# driver.net
KiCad netlist of a schematic drawn in EAGLE
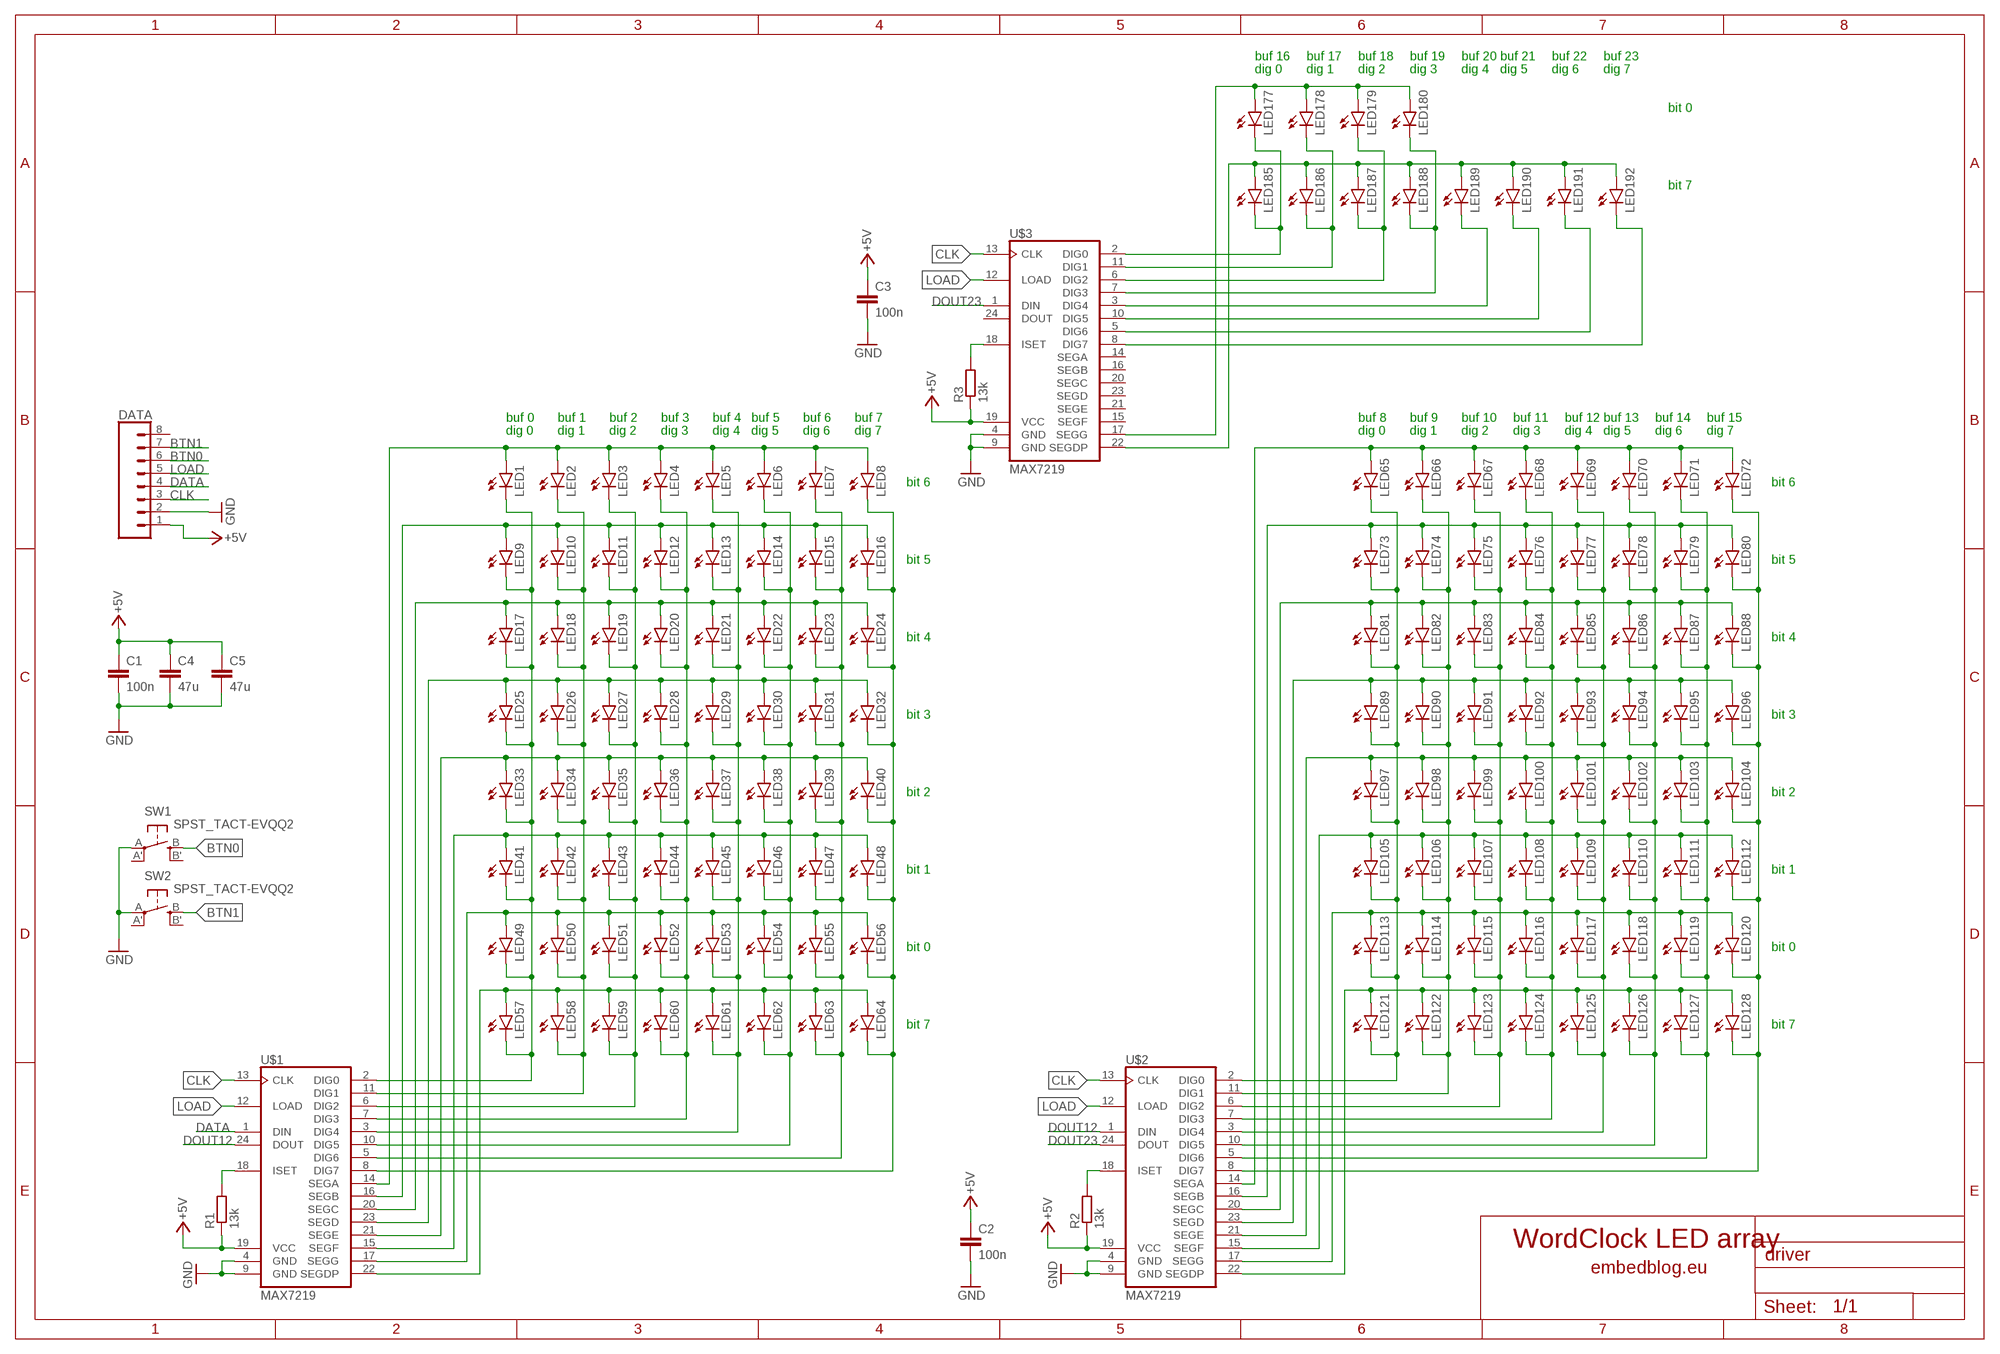
[diagram p0: schematic, sheet 1]

(export (version "E")
  (design (tool "Eeschema 10.0.6"))
  (components
    (comp (ref "C1")
      (value "100n")
      (footprint "eagle-import:C1206")
      (libsource (lib "eagle-import") (part "C-EUC1206"))
    )
    (comp (ref "C2")
      (value "100n")
      (footprint "eagle-import:C1206")
      (libsource (lib "eagle-import") (part "C-EUC1206"))
    )
    (comp (ref "C3")
      (value "100n")
      (footprint "eagle-import:C1206")
      (libsource (lib "eagle-import") (part "C-EUC1206"))
    )
    (comp (ref "C4")
      (value "47u")
      (footprint "eagle-import:C1206")
      (libsource (lib "eagle-import") (part "C-EUC1206"))
    )
    (comp (ref "C5")
      (value "47u")
      (footprint "eagle-import:C1206")
      (libsource (lib "eagle-import") (part "C-EUC1206"))
    )
    (comp (ref "DATA")
      (value "CONN_08\"")
      (footprint "eagle-import:1X08")
      (libsource (lib "eagle-import") (part "CONN_08{dblquote}"))
    )
    (comp (ref "LED1")
      (value "LEDCHIPLED_1206")
      (footprint "eagle-import:CHIPLED_1206")
      (libsource (lib "eagle-import") (part "LEDCHIPLED_1206"))
    )
    (comp (ref "LED2")
      (value "LEDCHIPLED_1206")
      (footprint "eagle-import:CHIPLED_1206")
      (libsource (lib "eagle-import") (part "LEDCHIPLED_1206"))
    )
    (comp (ref "LED3")
      (value "LEDCHIPLED_1206")
      (footprint "eagle-import:CHIPLED_1206")
      (libsource (lib "eagle-import") (part "LEDCHIPLED_1206"))
    )
    (comp (ref "LED4")
      (value "LEDCHIPLED_1206")
      (footprint "eagle-import:CHIPLED_1206")
      (libsource (lib "eagle-import") (part "LEDCHIPLED_1206"))
    )
    (comp (ref "LED5")
      (value "LEDCHIPLED_1206")
      (footprint "eagle-import:CHIPLED_1206")
      (libsource (lib "eagle-import") (part "LEDCHIPLED_1206"))
    )
    (comp (ref "LED6")
      (value "LEDCHIPLED_1206")
      (footprint "eagle-import:CHIPLED_1206")
      (libsource (lib "eagle-import") (part "LEDCHIPLED_1206"))
    )
    (comp (ref "LED7")
      (value "LEDCHIPLED_1206")
      (footprint "eagle-import:CHIPLED_1206")
      (libsource (lib "eagle-import") (part "LEDCHIPLED_1206"))
    )
    (comp (ref "LED8")
      (value "LEDCHIPLED_1206")
      (footprint "eagle-import:CHIPLED_1206")
      (libsource (lib "eagle-import") (part "LEDCHIPLED_1206"))
    )
    (comp (ref "LED9")
      (value "LEDCHIPLED_1206")
      (footprint "eagle-import:CHIPLED_1206")
      (libsource (lib "eagle-import") (part "LEDCHIPLED_1206"))
    )
    (comp (ref "LED10")
      (value "LEDCHIPLED_1206")
      (footprint "eagle-import:CHIPLED_1206")
      (libsource (lib "eagle-import") (part "LEDCHIPLED_1206"))
    )
    (comp (ref "LED11")
      (value "LEDCHIPLED_1206")
      (footprint "eagle-import:CHIPLED_1206")
      (libsource (lib "eagle-import") (part "LEDCHIPLED_1206"))
    )
    (comp (ref "LED12")
      (value "LEDCHIPLED_1206")
      (footprint "eagle-import:CHIPLED_1206")
      (libsource (lib "eagle-import") (part "LEDCHIPLED_1206"))
    )
    (comp (ref "LED13")
      (value "LEDCHIPLED_1206")
      (footprint "eagle-import:CHIPLED_1206")
      (libsource (lib "eagle-import") (part "LEDCHIPLED_1206"))
    )
    (comp (ref "LED14")
      (value "LEDCHIPLED_1206")
      (footprint "eagle-import:CHIPLED_1206")
      (libsource (lib "eagle-import") (part "LEDCHIPLED_1206"))
    )
    (comp (ref "LED15")
      (value "LEDCHIPLED_1206")
      (footprint "eagle-import:CHIPLED_1206")
      (libsource (lib "eagle-import") (part "LEDCHIPLED_1206"))
    )
    (comp (ref "LED16")
      (value "LEDCHIPLED_1206")
      (footprint "eagle-import:CHIPLED_1206")
      (libsource (lib "eagle-import") (part "LEDCHIPLED_1206"))
    )
    (comp (ref "LED17")
      (value "LEDCHIPLED_1206")
      (footprint "eagle-import:CHIPLED_1206")
      (libsource (lib "eagle-import") (part "LEDCHIPLED_1206"))
    )
    (comp (ref "LED18")
      (value "LEDCHIPLED_1206")
      (footprint "eagle-import:CHIPLED_1206")
      (libsource (lib "eagle-import") (part "LEDCHIPLED_1206"))
    )
    (comp (ref "LED19")
      (value "LEDCHIPLED_1206")
      (footprint "eagle-import:CHIPLED_1206")
      (libsource (lib "eagle-import") (part "LEDCHIPLED_1206"))
    )
    (comp (ref "LED20")
      (value "LEDCHIPLED_1206")
      (footprint "eagle-import:CHIPLED_1206")
      (libsource (lib "eagle-import") (part "LEDCHIPLED_1206"))
    )
    (comp (ref "LED21")
      (value "LEDCHIPLED_1206")
      (footprint "eagle-import:CHIPLED_1206")
      (libsource (lib "eagle-import") (part "LEDCHIPLED_1206"))
    )
    (comp (ref "LED22")
      (value "LEDCHIPLED_1206")
      (footprint "eagle-import:CHIPLED_1206")
      (libsource (lib "eagle-import") (part "LEDCHIPLED_1206"))
    )
    (comp (ref "LED23")
      (value "LEDCHIPLED_1206")
      (footprint "eagle-import:CHIPLED_1206")
      (libsource (lib "eagle-import") (part "LEDCHIPLED_1206"))
    )
    (comp (ref "LED24")
      (value "LEDCHIPLED_1206")
      (footprint "eagle-import:CHIPLED_1206")
      (libsource (lib "eagle-import") (part "LEDCHIPLED_1206"))
    )
    (comp (ref "LED25")
      (value "LEDCHIPLED_1206")
      (footprint "eagle-import:CHIPLED_1206")
      (libsource (lib "eagle-import") (part "LEDCHIPLED_1206"))
    )
    (comp (ref "LED26")
      (value "LEDCHIPLED_1206")
      (footprint "eagle-import:CHIPLED_1206")
      (libsource (lib "eagle-import") (part "LEDCHIPLED_1206"))
    )
    (comp (ref "LED27")
      (value "LEDCHIPLED_1206")
      (footprint "eagle-import:CHIPLED_1206")
      (libsource (lib "eagle-import") (part "LEDCHIPLED_1206"))
    )
    (comp (ref "LED28")
      (value "LEDCHIPLED_1206")
      (footprint "eagle-import:CHIPLED_1206")
      (libsource (lib "eagle-import") (part "LEDCHIPLED_1206"))
    )
    (comp (ref "LED29")
      (value "LEDCHIPLED_1206")
      (footprint "eagle-import:CHIPLED_1206")
      (libsource (lib "eagle-import") (part "LEDCHIPLED_1206"))
    )
    (comp (ref "LED30")
      (value "LEDCHIPLED_1206")
      (footprint "eagle-import:CHIPLED_1206")
      (libsource (lib "eagle-import") (part "LEDCHIPLED_1206"))
    )
    (comp (ref "LED31")
      (value "LEDCHIPLED_1206")
      (footprint "eagle-import:CHIPLED_1206")
      (libsource (lib "eagle-import") (part "LEDCHIPLED_1206"))
    )
    (comp (ref "LED32")
      (value "LEDCHIPLED_1206")
      (footprint "eagle-import:CHIPLED_1206")
      (libsource (lib "eagle-import") (part "LEDCHIPLED_1206"))
    )
    (comp (ref "LED33")
      (value "LEDCHIPLED_1206")
      (footprint "eagle-import:CHIPLED_1206")
      (libsource (lib "eagle-import") (part "LEDCHIPLED_1206"))
    )
    (comp (ref "LED34")
      (value "LEDCHIPLED_1206")
      (footprint "eagle-import:CHIPLED_1206")
      (libsource (lib "eagle-import") (part "LEDCHIPLED_1206"))
    )
    (comp (ref "LED35")
      (value "LEDCHIPLED_1206")
      (footprint "eagle-import:CHIPLED_1206")
      (libsource (lib "eagle-import") (part "LEDCHIPLED_1206"))
    )
    (comp (ref "LED36")
      (value "LEDCHIPLED_1206")
      (footprint "eagle-import:CHIPLED_1206")
      (libsource (lib "eagle-import") (part "LEDCHIPLED_1206"))
    )
    (comp (ref "LED37")
      (value "LEDCHIPLED_1206")
      (footprint "eagle-import:CHIPLED_1206")
      (libsource (lib "eagle-import") (part "LEDCHIPLED_1206"))
    )
    (comp (ref "LED38")
      (value "LEDCHIPLED_1206")
      (footprint "eagle-import:CHIPLED_1206")
      (libsource (lib "eagle-import") (part "LEDCHIPLED_1206"))
    )
    (comp (ref "LED39")
      (value "LEDCHIPLED_1206")
      (footprint "eagle-import:CHIPLED_1206")
      (libsource (lib "eagle-import") (part "LEDCHIPLED_1206"))
    )
    (comp (ref "LED40")
      (value "LEDCHIPLED_1206")
      (footprint "eagle-import:CHIPLED_1206")
      (libsource (lib "eagle-import") (part "LEDCHIPLED_1206"))
    )
    (comp (ref "LED41")
      (value "LEDCHIPLED_1206")
      (footprint "eagle-import:CHIPLED_1206")
      (libsource (lib "eagle-import") (part "LEDCHIPLED_1206"))
    )
    (comp (ref "LED42")
      (value "LEDCHIPLED_1206")
      (footprint "eagle-import:CHIPLED_1206")
      (libsource (lib "eagle-import") (part "LEDCHIPLED_1206"))
    )
    (comp (ref "LED43")
      (value "LEDCHIPLED_1206")
      (footprint "eagle-import:CHIPLED_1206")
      (libsource (lib "eagle-import") (part "LEDCHIPLED_1206"))
    )
    (comp (ref "LED44")
      (value "LEDCHIPLED_1206")
      (footprint "eagle-import:CHIPLED_1206")
      (libsource (lib "eagle-import") (part "LEDCHIPLED_1206"))
    )
    (comp (ref "LED45")
      (value "LEDCHIPLED_1206")
      (footprint "eagle-import:CHIPLED_1206")
      (libsource (lib "eagle-import") (part "LEDCHIPLED_1206"))
    )
    (comp (ref "LED46")
      (value "LEDCHIPLED_1206")
      (footprint "eagle-import:CHIPLED_1206")
      (libsource (lib "eagle-import") (part "LEDCHIPLED_1206"))
    )
    (comp (ref "LED47")
      (value "LEDCHIPLED_1206")
      (footprint "eagle-import:CHIPLED_1206")
      (libsource (lib "eagle-import") (part "LEDCHIPLED_1206"))
    )
    (comp (ref "LED48")
      (value "LEDCHIPLED_1206")
      (footprint "eagle-import:CHIPLED_1206")
      (libsource (lib "eagle-import") (part "LEDCHIPLED_1206"))
    )
    (comp (ref "LED49")
      (value "LEDCHIPLED_1206")
      (footprint "eagle-import:CHIPLED_1206")
      (libsource (lib "eagle-import") (part "LEDCHIPLED_1206"))
    )
    (comp (ref "LED50")
      (value "LEDCHIPLED_1206")
      (footprint "eagle-import:CHIPLED_1206")
      (libsource (lib "eagle-import") (part "LEDCHIPLED_1206"))
    )
    (comp (ref "LED51")
      (value "LEDCHIPLED_1206")
      (footprint "eagle-import:CHIPLED_1206")
      (libsource (lib "eagle-import") (part "LEDCHIPLED_1206"))
    )
    (comp (ref "LED52")
      (value "LEDCHIPLED_1206")
      (footprint "eagle-import:CHIPLED_1206")
      (libsource (lib "eagle-import") (part "LEDCHIPLED_1206"))
    )
    (comp (ref "LED53")
      (value "LEDCHIPLED_1206")
      (footprint "eagle-import:CHIPLED_1206")
      (libsource (lib "eagle-import") (part "LEDCHIPLED_1206"))
    )
    (comp (ref "LED54")
      (value "LEDCHIPLED_1206")
      (footprint "eagle-import:CHIPLED_1206")
      (libsource (lib "eagle-import") (part "LEDCHIPLED_1206"))
    )
    (comp (ref "LED55")
      (value "LEDCHIPLED_1206")
      (footprint "eagle-import:CHIPLED_1206")
      (libsource (lib "eagle-import") (part "LEDCHIPLED_1206"))
    )
    (comp (ref "LED56")
      (value "LEDCHIPLED_1206")
      (footprint "eagle-import:CHIPLED_1206")
      (libsource (lib "eagle-import") (part "LEDCHIPLED_1206"))
    )
    (comp (ref "LED57")
      (value "LEDCHIPLED_1206")
      (footprint "eagle-import:CHIPLED_1206")
      (libsource (lib "eagle-import") (part "LEDCHIPLED_1206"))
    )
    (comp (ref "LED58")
      (value "LEDCHIPLED_1206")
      (footprint "eagle-import:CHIPLED_1206")
      (libsource (lib "eagle-import") (part "LEDCHIPLED_1206"))
    )
    (comp (ref "LED59")
      (value "LEDCHIPLED_1206")
      (footprint "eagle-import:CHIPLED_1206")
      (libsource (lib "eagle-import") (part "LEDCHIPLED_1206"))
    )
    (comp (ref "LED60")
      (value "LEDCHIPLED_1206")
      (footprint "eagle-import:CHIPLED_1206")
      (libsource (lib "eagle-import") (part "LEDCHIPLED_1206"))
    )
    (comp (ref "LED61")
      (value "LEDCHIPLED_1206")
      (footprint "eagle-import:CHIPLED_1206")
      (libsource (lib "eagle-import") (part "LEDCHIPLED_1206"))
    )
    (comp (ref "LED62")
      (value "LEDCHIPLED_1206")
      (footprint "eagle-import:CHIPLED_1206")
      (libsource (lib "eagle-import") (part "LEDCHIPLED_1206"))
    )
    (comp (ref "LED63")
      (value "LEDCHIPLED_1206")
      (footprint "eagle-import:CHIPLED_1206")
      (libsource (lib "eagle-import") (part "LEDCHIPLED_1206"))
    )
    (comp (ref "LED64")
      (value "LEDCHIPLED_1206")
      (footprint "eagle-import:CHIPLED_1206")
      (libsource (lib "eagle-import") (part "LEDCHIPLED_1206"))
    )
    (comp (ref "LED65")
      (value "LEDCHIPLED_1206")
      (footprint "eagle-import:CHIPLED_1206")
      (libsource (lib "eagle-import") (part "LEDCHIPLED_1206"))
    )
    (comp (ref "LED66")
      (value "LEDCHIPLED_1206")
      (footprint "eagle-import:CHIPLED_1206")
      (libsource (lib "eagle-import") (part "LEDCHIPLED_1206"))
    )
    (comp (ref "LED67")
      (value "LEDCHIPLED_1206")
      (footprint "eagle-import:CHIPLED_1206")
      (libsource (lib "eagle-import") (part "LEDCHIPLED_1206"))
    )
    (comp (ref "LED68")
      (value "LEDCHIPLED_1206")
      (footprint "eagle-import:CHIPLED_1206")
      (libsource (lib "eagle-import") (part "LEDCHIPLED_1206"))
    )
    (comp (ref "LED69")
      (value "LEDCHIPLED_1206")
      (footprint "eagle-import:CHIPLED_1206")
      (libsource (lib "eagle-import") (part "LEDCHIPLED_1206"))
    )
    (comp (ref "LED70")
      (value "LEDCHIPLED_1206")
      (footprint "eagle-import:CHIPLED_1206")
      (libsource (lib "eagle-import") (part "LEDCHIPLED_1206"))
    )
    (comp (ref "LED71")
      (value "LEDCHIPLED_1206")
      (footprint "eagle-import:CHIPLED_1206")
      (libsource (lib "eagle-import") (part "LEDCHIPLED_1206"))
    )
    (comp (ref "LED72")
      (value "LEDCHIPLED_1206")
      (footprint "eagle-import:CHIPLED_1206")
      (libsource (lib "eagle-import") (part "LEDCHIPLED_1206"))
    )
    (comp (ref "LED73")
      (value "LEDCHIPLED_1206")
      (footprint "eagle-import:CHIPLED_1206")
      (libsource (lib "eagle-import") (part "LEDCHIPLED_1206"))
    )
    (comp (ref "LED74")
      (value "LEDCHIPLED_1206")
      (footprint "eagle-import:CHIPLED_1206")
      (libsource (lib "eagle-import") (part "LEDCHIPLED_1206"))
    )
    (comp (ref "LED75")
      (value "LEDCHIPLED_1206")
      (footprint "eagle-import:CHIPLED_1206")
      (libsource (lib "eagle-import") (part "LEDCHIPLED_1206"))
    )
    (comp (ref "LED76")
      (value "LEDCHIPLED_1206")
      (footprint "eagle-import:CHIPLED_1206")
      (libsource (lib "eagle-import") (part "LEDCHIPLED_1206"))
    )
    (comp (ref "LED77")
      (value "LEDCHIPLED_1206")
      (footprint "eagle-import:CHIPLED_1206")
      (libsource (lib "eagle-import") (part "LEDCHIPLED_1206"))
    )
    (comp (ref "LED78")
      (value "LEDCHIPLED_1206")
      (footprint "eagle-import:CHIPLED_1206")
      (libsource (lib "eagle-import") (part "LEDCHIPLED_1206"))
    )
    (comp (ref "LED79")
      (value "LEDCHIPLED_1206")
      (footprint "eagle-import:CHIPLED_1206")
      (libsource (lib "eagle-import") (part "LEDCHIPLED_1206"))
    )
    (comp (ref "LED80")
      (value "LEDCHIPLED_1206")
      (footprint "eagle-import:CHIPLED_1206")
      (libsource (lib "eagle-import") (part "LEDCHIPLED_1206"))
    )
    (comp (ref "LED81")
      (value "LEDCHIPLED_1206")
      (footprint "eagle-import:CHIPLED_1206")
      (libsource (lib "eagle-import") (part "LEDCHIPLED_1206"))
    )
    (comp (ref "LED82")
      (value "LEDCHIPLED_1206")
      (footprint "eagle-import:CHIPLED_1206")
      (libsource (lib "eagle-import") (part "LEDCHIPLED_1206"))
    )
    (comp (ref "LED83")
      (value "LEDCHIPLED_1206")
      (footprint "eagle-import:CHIPLED_1206")
      (libsource (lib "eagle-import") (part "LEDCHIPLED_1206"))
    )
    (comp (ref "LED84")
      (value "LEDCHIPLED_1206")
      (footprint "eagle-import:CHIPLED_1206")
      (libsource (lib "eagle-import") (part "LEDCHIPLED_1206"))
    )
    (comp (ref "LED85")
      (value "LEDCHIPLED_1206")
      (footprint "eagle-import:CHIPLED_1206")
      (libsource (lib "eagle-import") (part "LEDCHIPLED_1206"))
    )
    (comp (ref "LED86")
      (value "LEDCHIPLED_1206")
      (footprint "eagle-import:CHIPLED_1206")
      (libsource (lib "eagle-import") (part "LEDCHIPLED_1206"))
    )
    (comp (ref "LED87")
      (value "LEDCHIPLED_1206")
      (footprint "eagle-import:CHIPLED_1206")
      (libsource (lib "eagle-import") (part "LEDCHIPLED_1206"))
    )
    (comp (ref "LED88")
      (value "LEDCHIPLED_1206")
      (footprint "eagle-import:CHIPLED_1206")
      (libsource (lib "eagle-import") (part "LEDCHIPLED_1206"))
    )
    (comp (ref "LED89")
      (value "LEDCHIPLED_1206")
      (footprint "eagle-import:CHIPLED_1206")
      (libsource (lib "eagle-import") (part "LEDCHIPLED_1206"))
    )
    (comp (ref "LED90")
      (value "LEDCHIPLED_1206")
      (footprint "eagle-import:CHIPLED_1206")
      (libsource (lib "eagle-import") (part "LEDCHIPLED_1206"))
    )
    (comp (ref "LED91")
      (value "LEDCHIPLED_1206")
      (footprint "eagle-import:CHIPLED_1206")
      (libsource (lib "eagle-import") (part "LEDCHIPLED_1206"))
    )
    (comp (ref "LED92")
      (value "LEDCHIPLED_1206")
      (footprint "eagle-import:CHIPLED_1206")
      (libsource (lib "eagle-import") (part "LEDCHIPLED_1206"))
    )
    (comp (ref "LED93")
      (value "LEDCHIPLED_1206")
      (footprint "eagle-import:CHIPLED_1206")
      (libsource (lib "eagle-import") (part "LEDCHIPLED_1206"))
    )
    (comp (ref "LED94")
      (value "LEDCHIPLED_1206")
      (footprint "eagle-import:CHIPLED_1206")
      (libsource (lib "eagle-import") (part "LEDCHIPLED_1206"))
    )
    (comp (ref "LED95")
      (value "LEDCHIPLED_1206")
      (footprint "eagle-import:CHIPLED_1206")
      (libsource (lib "eagle-import") (part "LEDCHIPLED_1206"))
    )
    (comp (ref "LED96")
      (value "LEDCHIPLED_1206")
      (footprint "eagle-import:CHIPLED_1206")
      (libsource (lib "eagle-import") (part "LEDCHIPLED_1206"))
    )
    (comp (ref "LED97")
      (value "LEDCHIPLED_1206")
      (footprint "eagle-import:CHIPLED_1206")
      (libsource (lib "eagle-import") (part "LEDCHIPLED_1206"))
    )
    (comp (ref "LED98")
      (value "LEDCHIPLED_1206")
      (footprint "eagle-import:CHIPLED_1206")
      (libsource (lib "eagle-import") (part "LEDCHIPLED_1206"))
    )
    (comp (ref "LED99")
      (value "LEDCHIPLED_1206")
      (footprint "eagle-import:CHIPLED_1206")
      (libsource (lib "eagle-import") (part "LEDCHIPLED_1206"))
    )
    (comp (ref "LED100")
      (value "LEDCHIPLED_1206")
      (footprint "eagle-import:CHIPLED_1206")
      (libsource (lib "eagle-import") (part "LEDCHIPLED_1206"))
    )
    (comp (ref "LED101")
      (value "LEDCHIPLED_1206")
      (footprint "eagle-import:CHIPLED_1206")
      (libsource (lib "eagle-import") (part "LEDCHIPLED_1206"))
    )
    (comp (ref "LED102")
      (value "LEDCHIPLED_1206")
      (footprint "eagle-import:CHIPLED_1206")
      (libsource (lib "eagle-import") (part "LEDCHIPLED_1206"))
    )
    (comp (ref "LED103")
      (value "LEDCHIPLED_1206")
      (footprint "eagle-import:CHIPLED_1206")
      (libsource (lib "eagle-import") (part "LEDCHIPLED_1206"))
    )
    (comp (ref "LED104")
      (value "LEDCHIPLED_1206")
      (footprint "eagle-import:CHIPLED_1206")
      (libsource (lib "eagle-import") (part "LEDCHIPLED_1206"))
    )
    (comp (ref "LED105")
      (value "LEDCHIPLED_1206")
      (footprint "eagle-import:CHIPLED_1206")
      (libsource (lib "eagle-import") (part "LEDCHIPLED_1206"))
    )
    (comp (ref "LED106")
      (value "LEDCHIPLED_1206")
      (footprint "eagle-import:CHIPLED_1206")
      (libsource (lib "eagle-import") (part "LEDCHIPLED_1206"))
    )
    (comp (ref "LED107")
      (value "LEDCHIPLED_1206")
      (footprint "eagle-import:CHIPLED_1206")
      (libsource (lib "eagle-import") (part "LEDCHIPLED_1206"))
    )
    (comp (ref "LED108")
      (value "LEDCHIPLED_1206")
      (footprint "eagle-import:CHIPLED_1206")
      (libsource (lib "eagle-import") (part "LEDCHIPLED_1206"))
    )
    (comp (ref "LED109")
      (value "LEDCHIPLED_1206")
      (footprint "eagle-import:CHIPLED_1206")
      (libsource (lib "eagle-import") (part "LEDCHIPLED_1206"))
    )
    (comp (ref "LED110")
      (value "LEDCHIPLED_1206")
      (footprint "eagle-import:CHIPLED_1206")
      (libsource (lib "eagle-import") (part "LEDCHIPLED_1206"))
    )
    (comp (ref "LED111")
      (value "LEDCHIPLED_1206")
      (footprint "eagle-import:CHIPLED_1206")
      (libsource (lib "eagle-import") (part "LEDCHIPLED_1206"))
    )
    (comp (ref "LED112")
      (value "LEDCHIPLED_1206")
      (footprint "eagle-import:CHIPLED_1206")
      (libsource (lib "eagle-import") (part "LEDCHIPLED_1206"))
    )
    (comp (ref "LED113")
      (value "LEDCHIPLED_1206")
      (footprint "eagle-import:CHIPLED_1206")
      (libsource (lib "eagle-import") (part "LEDCHIPLED_1206"))
    )
    (comp (ref "LED114")
      (value "LEDCHIPLED_1206")
      (footprint "eagle-import:CHIPLED_1206")
      (libsource (lib "eagle-import") (part "LEDCHIPLED_1206"))
    )
    (comp (ref "LED115")
      (value "LEDCHIPLED_1206")
      (footprint "eagle-import:CHIPLED_1206")
      (libsource (lib "eagle-import") (part "LEDCHIPLED_1206"))
    )
    (comp (ref "LED116")
      (value "LEDCHIPLED_1206")
      (footprint "eagle-import:CHIPLED_1206")
      (libsource (lib "eagle-import") (part "LEDCHIPLED_1206"))
    )
    (comp (ref "LED117")
      (value "LEDCHIPLED_1206")
      (footprint "eagle-import:CHIPLED_1206")
      (libsource (lib "eagle-import") (part "LEDCHIPLED_1206"))
    )
    (comp (ref "LED118")
      (value "LEDCHIPLED_1206")
      (footprint "eagle-import:CHIPLED_1206")
      (libsource (lib "eagle-import") (part "LEDCHIPLED_1206"))
    )
    (comp (ref "LED119")
      (value "LEDCHIPLED_1206")
      (footprint "eagle-import:CHIPLED_1206")
      (libsource (lib "eagle-import") (part "LEDCHIPLED_1206"))
    )
    (comp (ref "LED120")
      (value "LEDCHIPLED_1206")
      (footprint "eagle-import:CHIPLED_1206")
      (libsource (lib "eagle-import") (part "LEDCHIPLED_1206"))
    )
    (comp (ref "LED121")
      (value "LEDCHIPLED_1206")
      (footprint "eagle-import:CHIPLED_1206")
      (libsource (lib "eagle-import") (part "LEDCHIPLED_1206"))
    )
    (comp (ref "LED122")
      (value "LEDCHIPLED_1206")
      (footprint "eagle-import:CHIPLED_1206")
      (libsource (lib "eagle-import") (part "LEDCHIPLED_1206"))
    )
    (comp (ref "LED123")
      (value "LEDCHIPLED_1206")
      (footprint "eagle-import:CHIPLED_1206")
      (libsource (lib "eagle-import") (part "LEDCHIPLED_1206"))
    )
    (comp (ref "LED124")
      (value "LEDCHIPLED_1206")
      (footprint "eagle-import:CHIPLED_1206")
      (libsource (lib "eagle-import") (part "LEDCHIPLED_1206"))
    )
    (comp (ref "LED125")
      (value "LEDCHIPLED_1206")
      (footprint "eagle-import:CHIPLED_1206")
      (libsource (lib "eagle-import") (part "LEDCHIPLED_1206"))
    )
    (comp (ref "LED126")
      (value "LEDCHIPLED_1206")
      (footprint "eagle-import:CHIPLED_1206")
      (libsource (lib "eagle-import") (part "LEDCHIPLED_1206"))
    )
    (comp (ref "LED127")
      (value "LEDCHIPLED_1206")
      (footprint "eagle-import:CHIPLED_1206")
      (libsource (lib "eagle-import") (part "LEDCHIPLED_1206"))
    )
    (comp (ref "LED128")
      (value "LEDCHIPLED_1206")
      (footprint "eagle-import:CHIPLED_1206")
      (libsource (lib "eagle-import") (part "LEDCHIPLED_1206"))
    )
    (comp (ref "LED177")
      (value "LEDCHIPLED_1206")
      (footprint "eagle-import:CHIPLED_1206")
      (libsource (lib "eagle-import") (part "LEDCHIPLED_1206"))
    )
    (comp (ref "LED178")
      (value "LEDCHIPLED_1206")
      (footprint "eagle-import:CHIPLED_1206")
      (libsource (lib "eagle-import") (part "LEDCHIPLED_1206"))
    )
    (comp (ref "LED179")
      (value "LEDCHIPLED_1206")
      (footprint "eagle-import:CHIPLED_1206")
      (libsource (lib "eagle-import") (part "LEDCHIPLED_1206"))
    )
    (comp (ref "LED180")
      (value "LEDCHIPLED_1206")
      (footprint "eagle-import:CHIPLED_1206")
      (libsource (lib "eagle-import") (part "LEDCHIPLED_1206"))
    )
    (comp (ref "LED185")
      (value "LEDCHIPLED_1206")
      (footprint "eagle-import:CHIPLED_1206")
      (libsource (lib "eagle-import") (part "LEDCHIPLED_1206"))
    )
    (comp (ref "LED186")
      (value "LEDCHIPLED_1206")
      (footprint "eagle-import:CHIPLED_1206")
      (libsource (lib "eagle-import") (part "LEDCHIPLED_1206"))
    )
    (comp (ref "LED187")
      (value "LEDCHIPLED_1206")
      (footprint "eagle-import:CHIPLED_1206")
      (libsource (lib "eagle-import") (part "LEDCHIPLED_1206"))
    )
    (comp (ref "LED188")
      (value "LEDCHIPLED_1206")
      (footprint "eagle-import:CHIPLED_1206")
      (libsource (lib "eagle-import") (part "LEDCHIPLED_1206"))
    )
    (comp (ref "LED189")
      (value "LEDCHIPLED_1206")
      (footprint "eagle-import:CHIPLED_1206")
      (libsource (lib "eagle-import") (part "LEDCHIPLED_1206"))
    )
    (comp (ref "LED190")
      (value "LEDCHIPLED_1206")
      (footprint "eagle-import:CHIPLED_1206")
      (libsource (lib "eagle-import") (part "LEDCHIPLED_1206"))
    )
    (comp (ref "LED191")
      (value "LEDCHIPLED_1206")
      (footprint "eagle-import:CHIPLED_1206")
      (libsource (lib "eagle-import") (part "LEDCHIPLED_1206"))
    )
    (comp (ref "LED192")
      (value "LEDCHIPLED_1206")
      (footprint "eagle-import:CHIPLED_1206")
      (libsource (lib "eagle-import") (part "LEDCHIPLED_1206"))
    )
    (comp (ref "R1")
      (value "13k")
      (footprint "eagle-import:R1206")
      (libsource (lib "eagle-import") (part "R-EU_R1206"))
    )
    (comp (ref "R2")
      (value "13k")
      (footprint "eagle-import:R1206")
      (libsource (lib "eagle-import") (part "R-EU_R1206"))
    )
    (comp (ref "R3")
      (value "13k")
      (footprint "eagle-import:R1206")
      (libsource (lib "eagle-import") (part "R-EU_R1206"))
    )
    (comp (ref "SW1")
      (value "SPST_TACT-EVQQ2")
      (footprint "eagle-import:EVQ-Q2")
      (libsource (lib "eagle-import") (part "SPST_TACT-EVQQ2"))
    )
    (comp (ref "SW2")
      (value "SPST_TACT-EVQQ2")
      (footprint "eagle-import:EVQ-Q2")
      (libsource (lib "eagle-import") (part "SPST_TACT-EVQQ2"))
    )
    (comp (ref "U$1")
      (value "MAX7219")
      (footprint "eagle-import:SO24W")
      (libsource (lib "eagle-import") (part "MAX7219"))
    )
    (comp (ref "U$2")
      (value "MAX7219")
      (footprint "eagle-import:SO24W")
      (libsource (lib "eagle-import") (part "MAX7219"))
    )
    (comp (ref "U$3")
      (value "MAX7219")
      (footprint "eagle-import:SO24W")
      (libsource (lib "eagle-import") (part "MAX7219"))
    )
  )
  (nets
    (net (code "1") (name "+5V") (class "Default")
      (node (ref "C1") (pin "1") (pinfunction "1_1") (pintype "passive"))
      (node (ref "C2") (pin "1") (pinfunction "1_1") (pintype "passive"))
      (node (ref "C3") (pin "1") (pinfunction "1_1") (pintype "passive"))
      (node (ref "C4") (pin "1") (pinfunction "1_1") (pintype "passive"))
      (node (ref "C5") (pin "1") (pinfunction "1_1") (pintype "passive"))
      (node (ref "DATA") (pin "1") (pinfunction "1_1") (pintype "passive"))
      (node (ref "R1") (pin "1") (pinfunction "1_1") (pintype "passive"))
      (node (ref "R2") (pin "1") (pinfunction "1_1") (pintype "passive"))
      (node (ref "R3") (pin "1") (pinfunction "1_1") (pintype "passive"))
      (node (ref "U$1") (pin "19") (pinfunction "VCC_19") (pintype "power_in"))
      (node (ref "U$2") (pin "19") (pinfunction "VCC_19") (pintype "power_in"))
      (node (ref "U$3") (pin "19") (pinfunction "VCC_19") (pintype "power_in"))
    )
    (net (code "2") (name "/DATA") (class "Default")
      (node (ref "DATA") (pin "4") (pinfunction "4_4") (pintype "passive"))
      (node (ref "U$1") (pin "1") (pinfunction "DIN_1") (pintype "input"))
    )
    (net (code "3") (name "/DOUT12") (class "Default")
      (node (ref "U$1") (pin "24") (pinfunction "DOUT_24") (pintype "output"))
      (node (ref "U$2") (pin "1") (pinfunction "DIN_1") (pintype "input"))
    )
    (net (code "4") (name "/DOUT23") (class "Default")
      (node (ref "U$2") (pin "24") (pinfunction "DOUT_24") (pintype "output"))
      (node (ref "U$3") (pin "1") (pinfunction "DIN_1") (pintype "input"))
    )
    (net (code "5") (name "BTN0") (class "Default")
      (node (ref "DATA") (pin "6") (pinfunction "6_6") (pintype "passive"))
      (node (ref "SW1") (pin "B") (pinfunction "S_B") (pintype "passive"))
    )
    (net (code "6") (name "BTN1") (class "Default")
      (node (ref "DATA") (pin "7") (pinfunction "7_7") (pintype "passive"))
      (node (ref "SW2") (pin "B") (pinfunction "S_B") (pintype "passive"))
    )
    (net (code "7") (name "CLK") (class "Default")
      (node (ref "DATA") (pin "3") (pinfunction "3_3") (pintype "passive"))
      (node (ref "U$1") (pin "13") (pinfunction "CLK_13") (pintype "input"))
      (node (ref "U$2") (pin "13") (pinfunction "CLK_13") (pintype "input"))
      (node (ref "U$3") (pin "13") (pinfunction "CLK_13") (pintype "input"))
    )
    (net (code "8") (name "GND") (class "Default")
      (node (ref "C1") (pin "2") (pinfunction "2_2") (pintype "passive"))
      (node (ref "C2") (pin "2") (pinfunction "2_2") (pintype "passive"))
      (node (ref "C3") (pin "2") (pinfunction "2_2") (pintype "passive"))
      (node (ref "C4") (pin "2") (pinfunction "2_2") (pintype "passive"))
      (node (ref "C5") (pin "2") (pinfunction "2_2") (pintype "passive"))
      (node (ref "DATA") (pin "2") (pinfunction "2_2") (pintype "passive"))
      (node (ref "SW1") (pin "A") (pinfunction "P_A") (pintype "passive"))
      (node (ref "SW2") (pin "A") (pinfunction "P_A") (pintype "passive"))
      (node (ref "U$1") (pin "4") (pinfunction "GND_4") (pintype "power_in"))
      (node (ref "U$1") (pin "9") (pinfunction "GND_9") (pintype "power_in"))
      (node (ref "U$2") (pin "4") (pinfunction "GND_4") (pintype "power_in"))
      (node (ref "U$2") (pin "9") (pinfunction "GND_9") (pintype "power_in"))
      (node (ref "U$3") (pin "4") (pinfunction "GND_4") (pintype "power_in"))
      (node (ref "U$3") (pin "9") (pinfunction "GND_9") (pintype "power_in"))
    )
    (net (code "9") (name "LOAD") (class "Default")
      (node (ref "DATA") (pin "5") (pinfunction "5_5") (pintype "passive"))
      (node (ref "U$1") (pin "12") (pinfunction "LOAD_12") (pintype "input"))
      (node (ref "U$2") (pin "12") (pinfunction "LOAD_12") (pintype "input"))
      (node (ref "U$3") (pin "12") (pinfunction "LOAD_12") (pintype "input"))
    )
    (net (code "10") (name "Net-(U$1-DIG0)") (class "Default")
      (node (ref "LED1") (pin "C") (pinfunction "C_C") (pintype "passive"))
      (node (ref "LED17") (pin "C") (pinfunction "C_C") (pintype "passive"))
      (node (ref "LED25") (pin "C") (pinfunction "C_C") (pintype "passive"))
      (node (ref "LED33") (pin "C") (pinfunction "C_C") (pintype "passive"))
      (node (ref "LED41") (pin "C") (pinfunction "C_C") (pintype "passive"))
      (node (ref "LED49") (pin "C") (pinfunction "C_C") (pintype "passive"))
      (node (ref "LED57") (pin "C") (pinfunction "C_C") (pintype "passive"))
      (node (ref "LED9") (pin "C") (pinfunction "C_C") (pintype "passive"))
      (node (ref "U$1") (pin "2") (pinfunction "DIG0_2") (pintype "output"))
    )
    (net (code "11") (name "Net-(U$1-DIG1)") (class "Default")
      (node (ref "LED10") (pin "C") (pinfunction "C_C") (pintype "passive"))
      (node (ref "LED18") (pin "C") (pinfunction "C_C") (pintype "passive"))
      (node (ref "LED2") (pin "C") (pinfunction "C_C") (pintype "passive"))
      (node (ref "LED26") (pin "C") (pinfunction "C_C") (pintype "passive"))
      (node (ref "LED34") (pin "C") (pinfunction "C_C") (pintype "passive"))
      (node (ref "LED42") (pin "C") (pinfunction "C_C") (pintype "passive"))
      (node (ref "LED50") (pin "C") (pinfunction "C_C") (pintype "passive"))
      (node (ref "LED58") (pin "C") (pinfunction "C_C") (pintype "passive"))
      (node (ref "U$1") (pin "11") (pinfunction "DIG1_11") (pintype "output"))
    )
    (net (code "12") (name "Net-(U$1-DIG2)") (class "Default")
      (node (ref "LED11") (pin "C") (pinfunction "C_C") (pintype "passive"))
      (node (ref "LED19") (pin "C") (pinfunction "C_C") (pintype "passive"))
      (node (ref "LED27") (pin "C") (pinfunction "C_C") (pintype "passive"))
      (node (ref "LED3") (pin "C") (pinfunction "C_C") (pintype "passive"))
      (node (ref "LED35") (pin "C") (pinfunction "C_C") (pintype "passive"))
      (node (ref "LED43") (pin "C") (pinfunction "C_C") (pintype "passive"))
      (node (ref "LED51") (pin "C") (pinfunction "C_C") (pintype "passive"))
      (node (ref "LED59") (pin "C") (pinfunction "C_C") (pintype "passive"))
      (node (ref "U$1") (pin "6") (pinfunction "DIG2_6") (pintype "output"))
    )
    (net (code "13") (name "Net-(U$1-DIG3)") (class "Default")
      (node (ref "LED12") (pin "C") (pinfunction "C_C") (pintype "passive"))
      (node (ref "LED20") (pin "C") (pinfunction "C_C") (pintype "passive"))
      (node (ref "LED28") (pin "C") (pinfunction "C_C") (pintype "passive"))
      (node (ref "LED36") (pin "C") (pinfunction "C_C") (pintype "passive"))
      (node (ref "LED4") (pin "C") (pinfunction "C_C") (pintype "passive"))
      (node (ref "LED44") (pin "C") (pinfunction "C_C") (pintype "passive"))
      (node (ref "LED52") (pin "C") (pinfunction "C_C") (pintype "passive"))
      (node (ref "LED60") (pin "C") (pinfunction "C_C") (pintype "passive"))
      (node (ref "U$1") (pin "7") (pinfunction "DIG3_7") (pintype "output"))
    )
    (net (code "14") (name "Net-(U$1-DIG4)") (class "Default")
      (node (ref "LED13") (pin "C") (pinfunction "C_C") (pintype "passive"))
      (node (ref "LED21") (pin "C") (pinfunction "C_C") (pintype "passive"))
      (node (ref "LED29") (pin "C") (pinfunction "C_C") (pintype "passive"))
      (node (ref "LED37") (pin "C") (pinfunction "C_C") (pintype "passive"))
      (node (ref "LED45") (pin "C") (pinfunction "C_C") (pintype "passive"))
      (node (ref "LED5") (pin "C") (pinfunction "C_C") (pintype "passive"))
      (node (ref "LED53") (pin "C") (pinfunction "C_C") (pintype "passive"))
      (node (ref "LED61") (pin "C") (pinfunction "C_C") (pintype "passive"))
      (node (ref "U$1") (pin "3") (pinfunction "DIG4_3") (pintype "output"))
    )
    (net (code "15") (name "Net-(U$1-DIG5)") (class "Default")
      (node (ref "LED14") (pin "C") (pinfunction "C_C") (pintype "passive"))
      (node (ref "LED22") (pin "C") (pinfunction "C_C") (pintype "passive"))
      (node (ref "LED30") (pin "C") (pinfunction "C_C") (pintype "passive"))
      (node (ref "LED38") (pin "C") (pinfunction "C_C") (pintype "passive"))
      (node (ref "LED46") (pin "C") (pinfunction "C_C") (pintype "passive"))
      (node (ref "LED54") (pin "C") (pinfunction "C_C") (pintype "passive"))
      (node (ref "LED6") (pin "C") (pinfunction "C_C") (pintype "passive"))
      (node (ref "LED62") (pin "C") (pinfunction "C_C") (pintype "passive"))
      (node (ref "U$1") (pin "10") (pinfunction "DIG5_10") (pintype "output"))
    )
    (net (code "16") (name "Net-(U$1-DIG6)") (class "Default")
      (node (ref "LED15") (pin "C") (pinfunction "C_C") (pintype "passive"))
      (node (ref "LED23") (pin "C") (pinfunction "C_C") (pintype "passive"))
      (node (ref "LED31") (pin "C") (pinfunction "C_C") (pintype "passive"))
      (node (ref "LED39") (pin "C") (pinfunction "C_C") (pintype "passive"))
      (node (ref "LED47") (pin "C") (pinfunction "C_C") (pintype "passive"))
      (node (ref "LED55") (pin "C") (pinfunction "C_C") (pintype "passive"))
      (node (ref "LED63") (pin "C") (pinfunction "C_C") (pintype "passive"))
      (node (ref "LED7") (pin "C") (pinfunction "C_C") (pintype "passive"))
      (node (ref "U$1") (pin "5") (pinfunction "DIG6_5") (pintype "output"))
    )
    (net (code "17") (name "Net-(U$1-DIG7)") (class "Default")
      (node (ref "LED16") (pin "C") (pinfunction "C_C") (pintype "passive"))
      (node (ref "LED24") (pin "C") (pinfunction "C_C") (pintype "passive"))
      (node (ref "LED32") (pin "C") (pinfunction "C_C") (pintype "passive"))
      (node (ref "LED40") (pin "C") (pinfunction "C_C") (pintype "passive"))
      (node (ref "LED48") (pin "C") (pinfunction "C_C") (pintype "passive"))
      (node (ref "LED56") (pin "C") (pinfunction "C_C") (pintype "passive"))
      (node (ref "LED64") (pin "C") (pinfunction "C_C") (pintype "passive"))
      (node (ref "LED8") (pin "C") (pinfunction "C_C") (pintype "passive"))
      (node (ref "U$1") (pin "8") (pinfunction "DIG7_8") (pintype "output"))
    )
    (net (code "18") (name "Net-(U$1-ISET)") (class "Default")
      (node (ref "R1") (pin "2") (pinfunction "2_2") (pintype "passive"))
      (node (ref "U$1") (pin "18") (pinfunction "ISET_18") (pintype "input"))
    )
    (net (code "19") (name "Net-(U$1-SEGA)") (class "Default")
      (node (ref "LED1") (pin "A") (pinfunction "A_A") (pintype "passive"))
      (node (ref "LED2") (pin "A") (pinfunction "A_A") (pintype "passive"))
      (node (ref "LED3") (pin "A") (pinfunction "A_A") (pintype "passive"))
      (node (ref "LED4") (pin "A") (pinfunction "A_A") (pintype "passive"))
      (node (ref "LED5") (pin "A") (pinfunction "A_A") (pintype "passive"))
      (node (ref "LED6") (pin "A") (pinfunction "A_A") (pintype "passive"))
      (node (ref "LED7") (pin "A") (pinfunction "A_A") (pintype "passive"))
      (node (ref "LED8") (pin "A") (pinfunction "A_A") (pintype "passive"))
      (node (ref "U$1") (pin "14") (pinfunction "SEGA_14") (pintype "output"))
    )
    (net (code "20") (name "Net-(U$1-SEGB)") (class "Default")
      (node (ref "LED10") (pin "A") (pinfunction "A_A") (pintype "passive"))
      (node (ref "LED11") (pin "A") (pinfunction "A_A") (pintype "passive"))
      (node (ref "LED12") (pin "A") (pinfunction "A_A") (pintype "passive"))
      (node (ref "LED13") (pin "A") (pinfunction "A_A") (pintype "passive"))
      (node (ref "LED14") (pin "A") (pinfunction "A_A") (pintype "passive"))
      (node (ref "LED15") (pin "A") (pinfunction "A_A") (pintype "passive"))
      (node (ref "LED16") (pin "A") (pinfunction "A_A") (pintype "passive"))
      (node (ref "LED9") (pin "A") (pinfunction "A_A") (pintype "passive"))
      (node (ref "U$1") (pin "16") (pinfunction "SEGB_16") (pintype "output"))
    )
    (net (code "21") (name "Net-(U$1-SEGC)") (class "Default")
      (node (ref "LED17") (pin "A") (pinfunction "A_A") (pintype "passive"))
      (node (ref "LED18") (pin "A") (pinfunction "A_A") (pintype "passive"))
      (node (ref "LED19") (pin "A") (pinfunction "A_A") (pintype "passive"))
      (node (ref "LED20") (pin "A") (pinfunction "A_A") (pintype "passive"))
      (node (ref "LED21") (pin "A") (pinfunction "A_A") (pintype "passive"))
      (node (ref "LED22") (pin "A") (pinfunction "A_A") (pintype "passive"))
      (node (ref "LED23") (pin "A") (pinfunction "A_A") (pintype "passive"))
      (node (ref "LED24") (pin "A") (pinfunction "A_A") (pintype "passive"))
      (node (ref "U$1") (pin "20") (pinfunction "SEGC_20") (pintype "output"))
    )
    (net (code "22") (name "Net-(U$1-SEGD)") (class "Default")
      (node (ref "LED25") (pin "A") (pinfunction "A_A") (pintype "passive"))
      (node (ref "LED26") (pin "A") (pinfunction "A_A") (pintype "passive"))
      (node (ref "LED27") (pin "A") (pinfunction "A_A") (pintype "passive"))
      (node (ref "LED28") (pin "A") (pinfunction "A_A") (pintype "passive"))
      (node (ref "LED29") (pin "A") (pinfunction "A_A") (pintype "passive"))
      (node (ref "LED30") (pin "A") (pinfunction "A_A") (pintype "passive"))
      (node (ref "LED31") (pin "A") (pinfunction "A_A") (pintype "passive"))
      (node (ref "LED32") (pin "A") (pinfunction "A_A") (pintype "passive"))
      (node (ref "U$1") (pin "23") (pinfunction "SEGD_23") (pintype "output"))
    )
    (net (code "23") (name "Net-(U$1-SEGDP)") (class "Default")
      (node (ref "LED57") (pin "A") (pinfunction "A_A") (pintype "passive"))
      (node (ref "LED58") (pin "A") (pinfunction "A_A") (pintype "passive"))
      (node (ref "LED59") (pin "A") (pinfunction "A_A") (pintype "passive"))
      (node (ref "LED60") (pin "A") (pinfunction "A_A") (pintype "passive"))
      (node (ref "LED61") (pin "A") (pinfunction "A_A") (pintype "passive"))
      (node (ref "LED62") (pin "A") (pinfunction "A_A") (pintype "passive"))
      (node (ref "LED63") (pin "A") (pinfunction "A_A") (pintype "passive"))
      (node (ref "LED64") (pin "A") (pinfunction "A_A") (pintype "passive"))
      (node (ref "U$1") (pin "22") (pinfunction "SEGDP_22") (pintype "output"))
    )
    (net (code "24") (name "Net-(U$1-SEGE)") (class "Default")
      (node (ref "LED33") (pin "A") (pinfunction "A_A") (pintype "passive"))
      (node (ref "LED34") (pin "A") (pinfunction "A_A") (pintype "passive"))
      (node (ref "LED35") (pin "A") (pinfunction "A_A") (pintype "passive"))
      (node (ref "LED36") (pin "A") (pinfunction "A_A") (pintype "passive"))
      (node (ref "LED37") (pin "A") (pinfunction "A_A") (pintype "passive"))
      (node (ref "LED38") (pin "A") (pinfunction "A_A") (pintype "passive"))
      (node (ref "LED39") (pin "A") (pinfunction "A_A") (pintype "passive"))
      (node (ref "LED40") (pin "A") (pinfunction "A_A") (pintype "passive"))
      (node (ref "U$1") (pin "21") (pinfunction "SEGE_21") (pintype "output"))
    )
    (net (code "25") (name "Net-(U$1-SEGF)") (class "Default")
      (node (ref "LED41") (pin "A") (pinfunction "A_A") (pintype "passive"))
      (node (ref "LED42") (pin "A") (pinfunction "A_A") (pintype "passive"))
      (node (ref "LED43") (pin "A") (pinfunction "A_A") (pintype "passive"))
      (node (ref "LED44") (pin "A") (pinfunction "A_A") (pintype "passive"))
      (node (ref "LED45") (pin "A") (pinfunction "A_A") (pintype "passive"))
      (node (ref "LED46") (pin "A") (pinfunction "A_A") (pintype "passive"))
      (node (ref "LED47") (pin "A") (pinfunction "A_A") (pintype "passive"))
      (node (ref "LED48") (pin "A") (pinfunction "A_A") (pintype "passive"))
      (node (ref "U$1") (pin "15") (pinfunction "SEGF_15") (pintype "output"))
    )
    (net (code "26") (name "Net-(U$1-SEGG)") (class "Default")
      (node (ref "LED49") (pin "A") (pinfunction "A_A") (pintype "passive"))
      (node (ref "LED50") (pin "A") (pinfunction "A_A") (pintype "passive"))
      (node (ref "LED51") (pin "A") (pinfunction "A_A") (pintype "passive"))
      (node (ref "LED52") (pin "A") (pinfunction "A_A") (pintype "passive"))
      (node (ref "LED53") (pin "A") (pinfunction "A_A") (pintype "passive"))
      (node (ref "LED54") (pin "A") (pinfunction "A_A") (pintype "passive"))
      (node (ref "LED55") (pin "A") (pinfunction "A_A") (pintype "passive"))
      (node (ref "LED56") (pin "A") (pinfunction "A_A") (pintype "passive"))
      (node (ref "U$1") (pin "17") (pinfunction "SEGG_17") (pintype "output"))
    )
    (net (code "27") (name "Net-(U$2-DIG0)") (class "Default")
      (node (ref "LED105") (pin "C") (pinfunction "C_C") (pintype "passive"))
      (node (ref "LED113") (pin "C") (pinfunction "C_C") (pintype "passive"))
      (node (ref "LED121") (pin "C") (pinfunction "C_C") (pintype "passive"))
      (node (ref "LED65") (pin "C") (pinfunction "C_C") (pintype "passive"))
      (node (ref "LED73") (pin "C") (pinfunction "C_C") (pintype "passive"))
      (node (ref "LED81") (pin "C") (pinfunction "C_C") (pintype "passive"))
      (node (ref "LED89") (pin "C") (pinfunction "C_C") (pintype "passive"))
      (node (ref "LED97") (pin "C") (pinfunction "C_C") (pintype "passive"))
      (node (ref "U$2") (pin "2") (pinfunction "DIG0_2") (pintype "output"))
    )
    (net (code "28") (name "Net-(U$2-DIG1)") (class "Default")
      (node (ref "LED106") (pin "C") (pinfunction "C_C") (pintype "passive"))
      (node (ref "LED114") (pin "C") (pinfunction "C_C") (pintype "passive"))
      (node (ref "LED122") (pin "C") (pinfunction "C_C") (pintype "passive"))
      (node (ref "LED66") (pin "C") (pinfunction "C_C") (pintype "passive"))
      (node (ref "LED74") (pin "C") (pinfunction "C_C") (pintype "passive"))
      (node (ref "LED82") (pin "C") (pinfunction "C_C") (pintype "passive"))
      (node (ref "LED90") (pin "C") (pinfunction "C_C") (pintype "passive"))
      (node (ref "LED98") (pin "C") (pinfunction "C_C") (pintype "passive"))
      (node (ref "U$2") (pin "11") (pinfunction "DIG1_11") (pintype "output"))
    )
    (net (code "29") (name "Net-(U$2-DIG2)") (class "Default")
      (node (ref "LED107") (pin "C") (pinfunction "C_C") (pintype "passive"))
      (node (ref "LED115") (pin "C") (pinfunction "C_C") (pintype "passive"))
      (node (ref "LED123") (pin "C") (pinfunction "C_C") (pintype "passive"))
      (node (ref "LED67") (pin "C") (pinfunction "C_C") (pintype "passive"))
      (node (ref "LED75") (pin "C") (pinfunction "C_C") (pintype "passive"))
      (node (ref "LED83") (pin "C") (pinfunction "C_C") (pintype "passive"))
      (node (ref "LED91") (pin "C") (pinfunction "C_C") (pintype "passive"))
      (node (ref "LED99") (pin "C") (pinfunction "C_C") (pintype "passive"))
      (node (ref "U$2") (pin "6") (pinfunction "DIG2_6") (pintype "output"))
    )
    (net (code "30") (name "Net-(U$2-DIG3)") (class "Default")
      (node (ref "LED100") (pin "C") (pinfunction "C_C") (pintype "passive"))
      (node (ref "LED108") (pin "C") (pinfunction "C_C") (pintype "passive"))
      (node (ref "LED116") (pin "C") (pinfunction "C_C") (pintype "passive"))
      (node (ref "LED124") (pin "C") (pinfunction "C_C") (pintype "passive"))
      (node (ref "LED68") (pin "C") (pinfunction "C_C") (pintype "passive"))
      (node (ref "LED76") (pin "C") (pinfunction "C_C") (pintype "passive"))
      (node (ref "LED84") (pin "C") (pinfunction "C_C") (pintype "passive"))
      (node (ref "LED92") (pin "C") (pinfunction "C_C") (pintype "passive"))
      (node (ref "U$2") (pin "7") (pinfunction "DIG3_7") (pintype "output"))
    )
    (net (code "31") (name "Net-(U$2-DIG4)") (class "Default")
      (node (ref "LED101") (pin "C") (pinfunction "C_C") (pintype "passive"))
      (node (ref "LED109") (pin "C") (pinfunction "C_C") (pintype "passive"))
      (node (ref "LED117") (pin "C") (pinfunction "C_C") (pintype "passive"))
      (node (ref "LED125") (pin "C") (pinfunction "C_C") (pintype "passive"))
      (node (ref "LED69") (pin "C") (pinfunction "C_C") (pintype "passive"))
      (node (ref "LED77") (pin "C") (pinfunction "C_C") (pintype "passive"))
      (node (ref "LED85") (pin "C") (pinfunction "C_C") (pintype "passive"))
      (node (ref "LED93") (pin "C") (pinfunction "C_C") (pintype "passive"))
      (node (ref "U$2") (pin "3") (pinfunction "DIG4_3") (pintype "output"))
    )
    (net (code "32") (name "Net-(U$2-DIG5)") (class "Default")
      (node (ref "LED102") (pin "C") (pinfunction "C_C") (pintype "passive"))
      (node (ref "LED110") (pin "C") (pinfunction "C_C") (pintype "passive"))
      (node (ref "LED118") (pin "C") (pinfunction "C_C") (pintype "passive"))
      (node (ref "LED126") (pin "C") (pinfunction "C_C") (pintype "passive"))
      (node (ref "LED70") (pin "C") (pinfunction "C_C") (pintype "passive"))
      (node (ref "LED78") (pin "C") (pinfunction "C_C") (pintype "passive"))
      (node (ref "LED86") (pin "C") (pinfunction "C_C") (pintype "passive"))
      (node (ref "LED94") (pin "C") (pinfunction "C_C") (pintype "passive"))
      (node (ref "U$2") (pin "10") (pinfunction "DIG5_10") (pintype "output"))
    )
    (net (code "33") (name "Net-(U$2-DIG6)") (class "Default")
      (node (ref "LED103") (pin "C") (pinfunction "C_C") (pintype "passive"))
      (node (ref "LED111") (pin "C") (pinfunction "C_C") (pintype "passive"))
      (node (ref "LED119") (pin "C") (pinfunction "C_C") (pintype "passive"))
      (node (ref "LED127") (pin "C") (pinfunction "C_C") (pintype "passive"))
      (node (ref "LED71") (pin "C") (pinfunction "C_C") (pintype "passive"))
      (node (ref "LED79") (pin "C") (pinfunction "C_C") (pintype "passive"))
      (node (ref "LED87") (pin "C") (pinfunction "C_C") (pintype "passive"))
      (node (ref "LED95") (pin "C") (pinfunction "C_C") (pintype "passive"))
      (node (ref "U$2") (pin "5") (pinfunction "DIG6_5") (pintype "output"))
    )
    (net (code "34") (name "Net-(U$2-DIG7)") (class "Default")
      (node (ref "LED104") (pin "C") (pinfunction "C_C") (pintype "passive"))
      (node (ref "LED112") (pin "C") (pinfunction "C_C") (pintype "passive"))
      (node (ref "LED120") (pin "C") (pinfunction "C_C") (pintype "passive"))
      (node (ref "LED128") (pin "C") (pinfunction "C_C") (pintype "passive"))
      (node (ref "LED72") (pin "C") (pinfunction "C_C") (pintype "passive"))
      (node (ref "LED80") (pin "C") (pinfunction "C_C") (pintype "passive"))
      (node (ref "LED88") (pin "C") (pinfunction "C_C") (pintype "passive"))
      (node (ref "LED96") (pin "C") (pinfunction "C_C") (pintype "passive"))
      (node (ref "U$2") (pin "8") (pinfunction "DIG7_8") (pintype "output"))
    )
    (net (code "35") (name "Net-(U$2-ISET)") (class "Default")
      (node (ref "R2") (pin "2") (pinfunction "2_2") (pintype "passive"))
      (node (ref "U$2") (pin "18") (pinfunction "ISET_18") (pintype "input"))
    )
    (net (code "36") (name "Net-(U$2-SEGA)") (class "Default")
      (node (ref "LED65") (pin "A") (pinfunction "A_A") (pintype "passive"))
      (node (ref "LED66") (pin "A") (pinfunction "A_A") (pintype "passive"))
      (node (ref "LED67") (pin "A") (pinfunction "A_A") (pintype "passive"))
      (node (ref "LED68") (pin "A") (pinfunction "A_A") (pintype "passive"))
      (node (ref "LED69") (pin "A") (pinfunction "A_A") (pintype "passive"))
      (node (ref "LED70") (pin "A") (pinfunction "A_A") (pintype "passive"))
      (node (ref "LED71") (pin "A") (pinfunction "A_A") (pintype "passive"))
      (node (ref "LED72") (pin "A") (pinfunction "A_A") (pintype "passive"))
      (node (ref "U$2") (pin "14") (pinfunction "SEGA_14") (pintype "output"))
    )
    (net (code "37") (name "Net-(U$2-SEGB)") (class "Default")
      (node (ref "LED73") (pin "A") (pinfunction "A_A") (pintype "passive"))
      (node (ref "LED74") (pin "A") (pinfunction "A_A") (pintype "passive"))
      (node (ref "LED75") (pin "A") (pinfunction "A_A") (pintype "passive"))
      (node (ref "LED76") (pin "A") (pinfunction "A_A") (pintype "passive"))
      (node (ref "LED77") (pin "A") (pinfunction "A_A") (pintype "passive"))
      (node (ref "LED78") (pin "A") (pinfunction "A_A") (pintype "passive"))
      (node (ref "LED79") (pin "A") (pinfunction "A_A") (pintype "passive"))
      (node (ref "LED80") (pin "A") (pinfunction "A_A") (pintype "passive"))
      (node (ref "U$2") (pin "16") (pinfunction "SEGB_16") (pintype "output"))
    )
    (net (code "38") (name "Net-(U$2-SEGC)") (class "Default")
      (node (ref "LED81") (pin "A") (pinfunction "A_A") (pintype "passive"))
      (node (ref "LED82") (pin "A") (pinfunction "A_A") (pintype "passive"))
      (node (ref "LED83") (pin "A") (pinfunction "A_A") (pintype "passive"))
      (node (ref "LED84") (pin "A") (pinfunction "A_A") (pintype "passive"))
      (node (ref "LED85") (pin "A") (pinfunction "A_A") (pintype "passive"))
      (node (ref "LED86") (pin "A") (pinfunction "A_A") (pintype "passive"))
      (node (ref "LED87") (pin "A") (pinfunction "A_A") (pintype "passive"))
      (node (ref "LED88") (pin "A") (pinfunction "A_A") (pintype "passive"))
      (node (ref "U$2") (pin "20") (pinfunction "SEGC_20") (pintype "output"))
    )
    (net (code "39") (name "Net-(U$2-SEGD)") (class "Default")
      (node (ref "LED89") (pin "A") (pinfunction "A_A") (pintype "passive"))
      (node (ref "LED90") (pin "A") (pinfunction "A_A") (pintype "passive"))
      (node (ref "LED91") (pin "A") (pinfunction "A_A") (pintype "passive"))
      (node (ref "LED92") (pin "A") (pinfunction "A_A") (pintype "passive"))
      (node (ref "LED93") (pin "A") (pinfunction "A_A") (pintype "passive"))
      (node (ref "LED94") (pin "A") (pinfunction "A_A") (pintype "passive"))
      (node (ref "LED95") (pin "A") (pinfunction "A_A") (pintype "passive"))
      (node (ref "LED96") (pin "A") (pinfunction "A_A") (pintype "passive"))
      (node (ref "U$2") (pin "23") (pinfunction "SEGD_23") (pintype "output"))
    )
    (net (code "40") (name "Net-(U$2-SEGDP)") (class "Default")
      (node (ref "LED121") (pin "A") (pinfunction "A_A") (pintype "passive"))
      (node (ref "LED122") (pin "A") (pinfunction "A_A") (pintype "passive"))
      (node (ref "LED123") (pin "A") (pinfunction "A_A") (pintype "passive"))
      (node (ref "LED124") (pin "A") (pinfunction "A_A") (pintype "passive"))
      (node (ref "LED125") (pin "A") (pinfunction "A_A") (pintype "passive"))
      (node (ref "LED126") (pin "A") (pinfunction "A_A") (pintype "passive"))
      (node (ref "LED127") (pin "A") (pinfunction "A_A") (pintype "passive"))
      (node (ref "LED128") (pin "A") (pinfunction "A_A") (pintype "passive"))
      (node (ref "U$2") (pin "22") (pinfunction "SEGDP_22") (pintype "output"))
    )
    (net (code "41") (name "Net-(U$2-SEGE)") (class "Default")
      (node (ref "LED100") (pin "A") (pinfunction "A_A") (pintype "passive"))
      (node (ref "LED101") (pin "A") (pinfunction "A_A") (pintype "passive"))
      (node (ref "LED102") (pin "A") (pinfunction "A_A") (pintype "passive"))
      (node (ref "LED103") (pin "A") (pinfunction "A_A") (pintype "passive"))
      (node (ref "LED104") (pin "A") (pinfunction "A_A") (pintype "passive"))
      (node (ref "LED97") (pin "A") (pinfunction "A_A") (pintype "passive"))
      (node (ref "LED98") (pin "A") (pinfunction "A_A") (pintype "passive"))
      (node (ref "LED99") (pin "A") (pinfunction "A_A") (pintype "passive"))
      (node (ref "U$2") (pin "21") (pinfunction "SEGE_21") (pintype "output"))
    )
    (net (code "42") (name "Net-(U$2-SEGF)") (class "Default")
      (node (ref "LED105") (pin "A") (pinfunction "A_A") (pintype "passive"))
      (node (ref "LED106") (pin "A") (pinfunction "A_A") (pintype "passive"))
      (node (ref "LED107") (pin "A") (pinfunction "A_A") (pintype "passive"))
      (node (ref "LED108") (pin "A") (pinfunction "A_A") (pintype "passive"))
      (node (ref "LED109") (pin "A") (pinfunction "A_A") (pintype "passive"))
      (node (ref "LED110") (pin "A") (pinfunction "A_A") (pintype "passive"))
      (node (ref "LED111") (pin "A") (pinfunction "A_A") (pintype "passive"))
      (node (ref "LED112") (pin "A") (pinfunction "A_A") (pintype "passive"))
      (node (ref "U$2") (pin "15") (pinfunction "SEGF_15") (pintype "output"))
    )
    (net (code "43") (name "Net-(U$2-SEGG)") (class "Default")
      (node (ref "LED113") (pin "A") (pinfunction "A_A") (pintype "passive"))
      (node (ref "LED114") (pin "A") (pinfunction "A_A") (pintype "passive"))
      (node (ref "LED115") (pin "A") (pinfunction "A_A") (pintype "passive"))
      (node (ref "LED116") (pin "A") (pinfunction "A_A") (pintype "passive"))
      (node (ref "LED117") (pin "A") (pinfunction "A_A") (pintype "passive"))
      (node (ref "LED118") (pin "A") (pinfunction "A_A") (pintype "passive"))
      (node (ref "LED119") (pin "A") (pinfunction "A_A") (pintype "passive"))
      (node (ref "LED120") (pin "A") (pinfunction "A_A") (pintype "passive"))
      (node (ref "U$2") (pin "17") (pinfunction "SEGG_17") (pintype "output"))
    )
    (net (code "44") (name "Net-(U$3-DIG0)") (class "Default")
      (node (ref "LED177") (pin "C") (pinfunction "C_C") (pintype "passive"))
      (node (ref "LED185") (pin "C") (pinfunction "C_C") (pintype "passive"))
      (node (ref "U$3") (pin "2") (pinfunction "DIG0_2") (pintype "output"))
    )
    (net (code "45") (name "Net-(U$3-DIG1)") (class "Default")
      (node (ref "LED178") (pin "C") (pinfunction "C_C") (pintype "passive"))
      (node (ref "LED186") (pin "C") (pinfunction "C_C") (pintype "passive"))
      (node (ref "U$3") (pin "11") (pinfunction "DIG1_11") (pintype "output"))
    )
    (net (code "46") (name "Net-(U$3-DIG2)") (class "Default")
      (node (ref "LED179") (pin "C") (pinfunction "C_C") (pintype "passive"))
      (node (ref "LED187") (pin "C") (pinfunction "C_C") (pintype "passive"))
      (node (ref "U$3") (pin "6") (pinfunction "DIG2_6") (pintype "output"))
    )
    (net (code "47") (name "Net-(U$3-DIG3)") (class "Default")
      (node (ref "LED180") (pin "C") (pinfunction "C_C") (pintype "passive"))
      (node (ref "LED188") (pin "C") (pinfunction "C_C") (pintype "passive"))
      (node (ref "U$3") (pin "7") (pinfunction "DIG3_7") (pintype "output"))
    )
    (net (code "48") (name "Net-(U$3-DIG4)") (class "Default")
      (node (ref "LED189") (pin "C") (pinfunction "C_C") (pintype "passive"))
      (node (ref "U$3") (pin "3") (pinfunction "DIG4_3") (pintype "output"))
    )
    (net (code "49") (name "Net-(U$3-DIG5)") (class "Default")
      (node (ref "LED190") (pin "C") (pinfunction "C_C") (pintype "passive"))
      (node (ref "U$3") (pin "10") (pinfunction "DIG5_10") (pintype "output"))
    )
    (net (code "50") (name "Net-(U$3-DIG6)") (class "Default")
      (node (ref "LED191") (pin "C") (pinfunction "C_C") (pintype "passive"))
      (node (ref "U$3") (pin "5") (pinfunction "DIG6_5") (pintype "output"))
    )
    (net (code "51") (name "Net-(U$3-DIG7)") (class "Default")
      (node (ref "LED192") (pin "C") (pinfunction "C_C") (pintype "passive"))
      (node (ref "U$3") (pin "8") (pinfunction "DIG7_8") (pintype "output"))
    )
    (net (code "52") (name "Net-(U$3-ISET)") (class "Default")
      (node (ref "R3") (pin "2") (pinfunction "2_2") (pintype "passive"))
      (node (ref "U$3") (pin "18") (pinfunction "ISET_18") (pintype "input"))
    )
    (net (code "53") (name "Net-(U$3-SEGDP)") (class "Default")
      (node (ref "LED185") (pin "A") (pinfunction "A_A") (pintype "passive"))
      (node (ref "LED186") (pin "A") (pinfunction "A_A") (pintype "passive"))
      (node (ref "LED187") (pin "A") (pinfunction "A_A") (pintype "passive"))
      (node (ref "LED188") (pin "A") (pinfunction "A_A") (pintype "passive"))
      (node (ref "LED189") (pin "A") (pinfunction "A_A") (pintype "passive"))
      (node (ref "LED190") (pin "A") (pinfunction "A_A") (pintype "passive"))
      (node (ref "LED191") (pin "A") (pinfunction "A_A") (pintype "passive"))
      (node (ref "LED192") (pin "A") (pinfunction "A_A") (pintype "passive"))
      (node (ref "U$3") (pin "22") (pinfunction "SEGDP_22") (pintype "output"))
    )
    (net (code "54") (name "Net-(U$3-SEGG)") (class "Default")
      (node (ref "LED177") (pin "A") (pinfunction "A_A") (pintype "passive"))
      (node (ref "LED178") (pin "A") (pinfunction "A_A") (pintype "passive"))
      (node (ref "LED179") (pin "A") (pinfunction "A_A") (pintype "passive"))
      (node (ref "LED180") (pin "A") (pinfunction "A_A") (pintype "passive"))
      (node (ref "U$3") (pin "17") (pinfunction "SEGG_17") (pintype "output"))
    )
    (net (code "55") (name "unconnected-(DATA-Pad8)") (class "Default")
      (node (ref "DATA") (pin "8") (pinfunction "8_8") (pintype "passive"))
    )
    (net (code "56") (name "unconnected-(SW1-P1-PadA')") (class "Default")
      (node (ref "SW1") (pin "A'") (pinfunction "P1_A'") (pintype "passive"))
    )
    (net (code "57") (name "unconnected-(SW1-S1-PadB')") (class "Default")
      (node (ref "SW1") (pin "B'") (pinfunction "S1_B'") (pintype "passive"))
    )
    (net (code "58") (name "unconnected-(SW2-P1-PadA')") (class "Default")
      (node (ref "SW2") (pin "A'") (pinfunction "P1_A'") (pintype "passive"))
    )
    (net (code "59") (name "unconnected-(SW2-S1-PadB')") (class "Default")
      (node (ref "SW2") (pin "B'") (pinfunction "S1_B'") (pintype "passive"))
    )
    (net (code "60") (name "unconnected-(U$3-DOUT-Pad24)") (class "Default")
      (node (ref "U$3") (pin "24") (pinfunction "DOUT_24") (pintype "output"))
    )
    (net (code "61") (name "unconnected-(U$3-SEGA-Pad14)") (class "Default")
      (node (ref "U$3") (pin "14") (pinfunction "SEGA_14") (pintype "output"))
    )
    (net (code "62") (name "unconnected-(U$3-SEGB-Pad16)") (class "Default")
      (node (ref "U$3") (pin "16") (pinfunction "SEGB_16") (pintype "output"))
    )
    (net (code "63") (name "unconnected-(U$3-SEGC-Pad20)") (class "Default")
      (node (ref "U$3") (pin "20") (pinfunction "SEGC_20") (pintype "output"))
    )
    (net (code "64") (name "unconnected-(U$3-SEGD-Pad23)") (class "Default")
      (node (ref "U$3") (pin "23") (pinfunction "SEGD_23") (pintype "output"))
    )
    (net (code "65") (name "unconnected-(U$3-SEGE-Pad21)") (class "Default")
      (node (ref "U$3") (pin "21") (pinfunction "SEGE_21") (pintype "output"))
    )
    (net (code "66") (name "unconnected-(U$3-SEGF-Pad15)") (class "Default")
      (node (ref "U$3") (pin "15") (pinfunction "SEGF_15") (pintype "output"))
    )
  )
)
